# GEM_AFE_128.net
KiCad netlist of a schematic drawn in Altium Designer
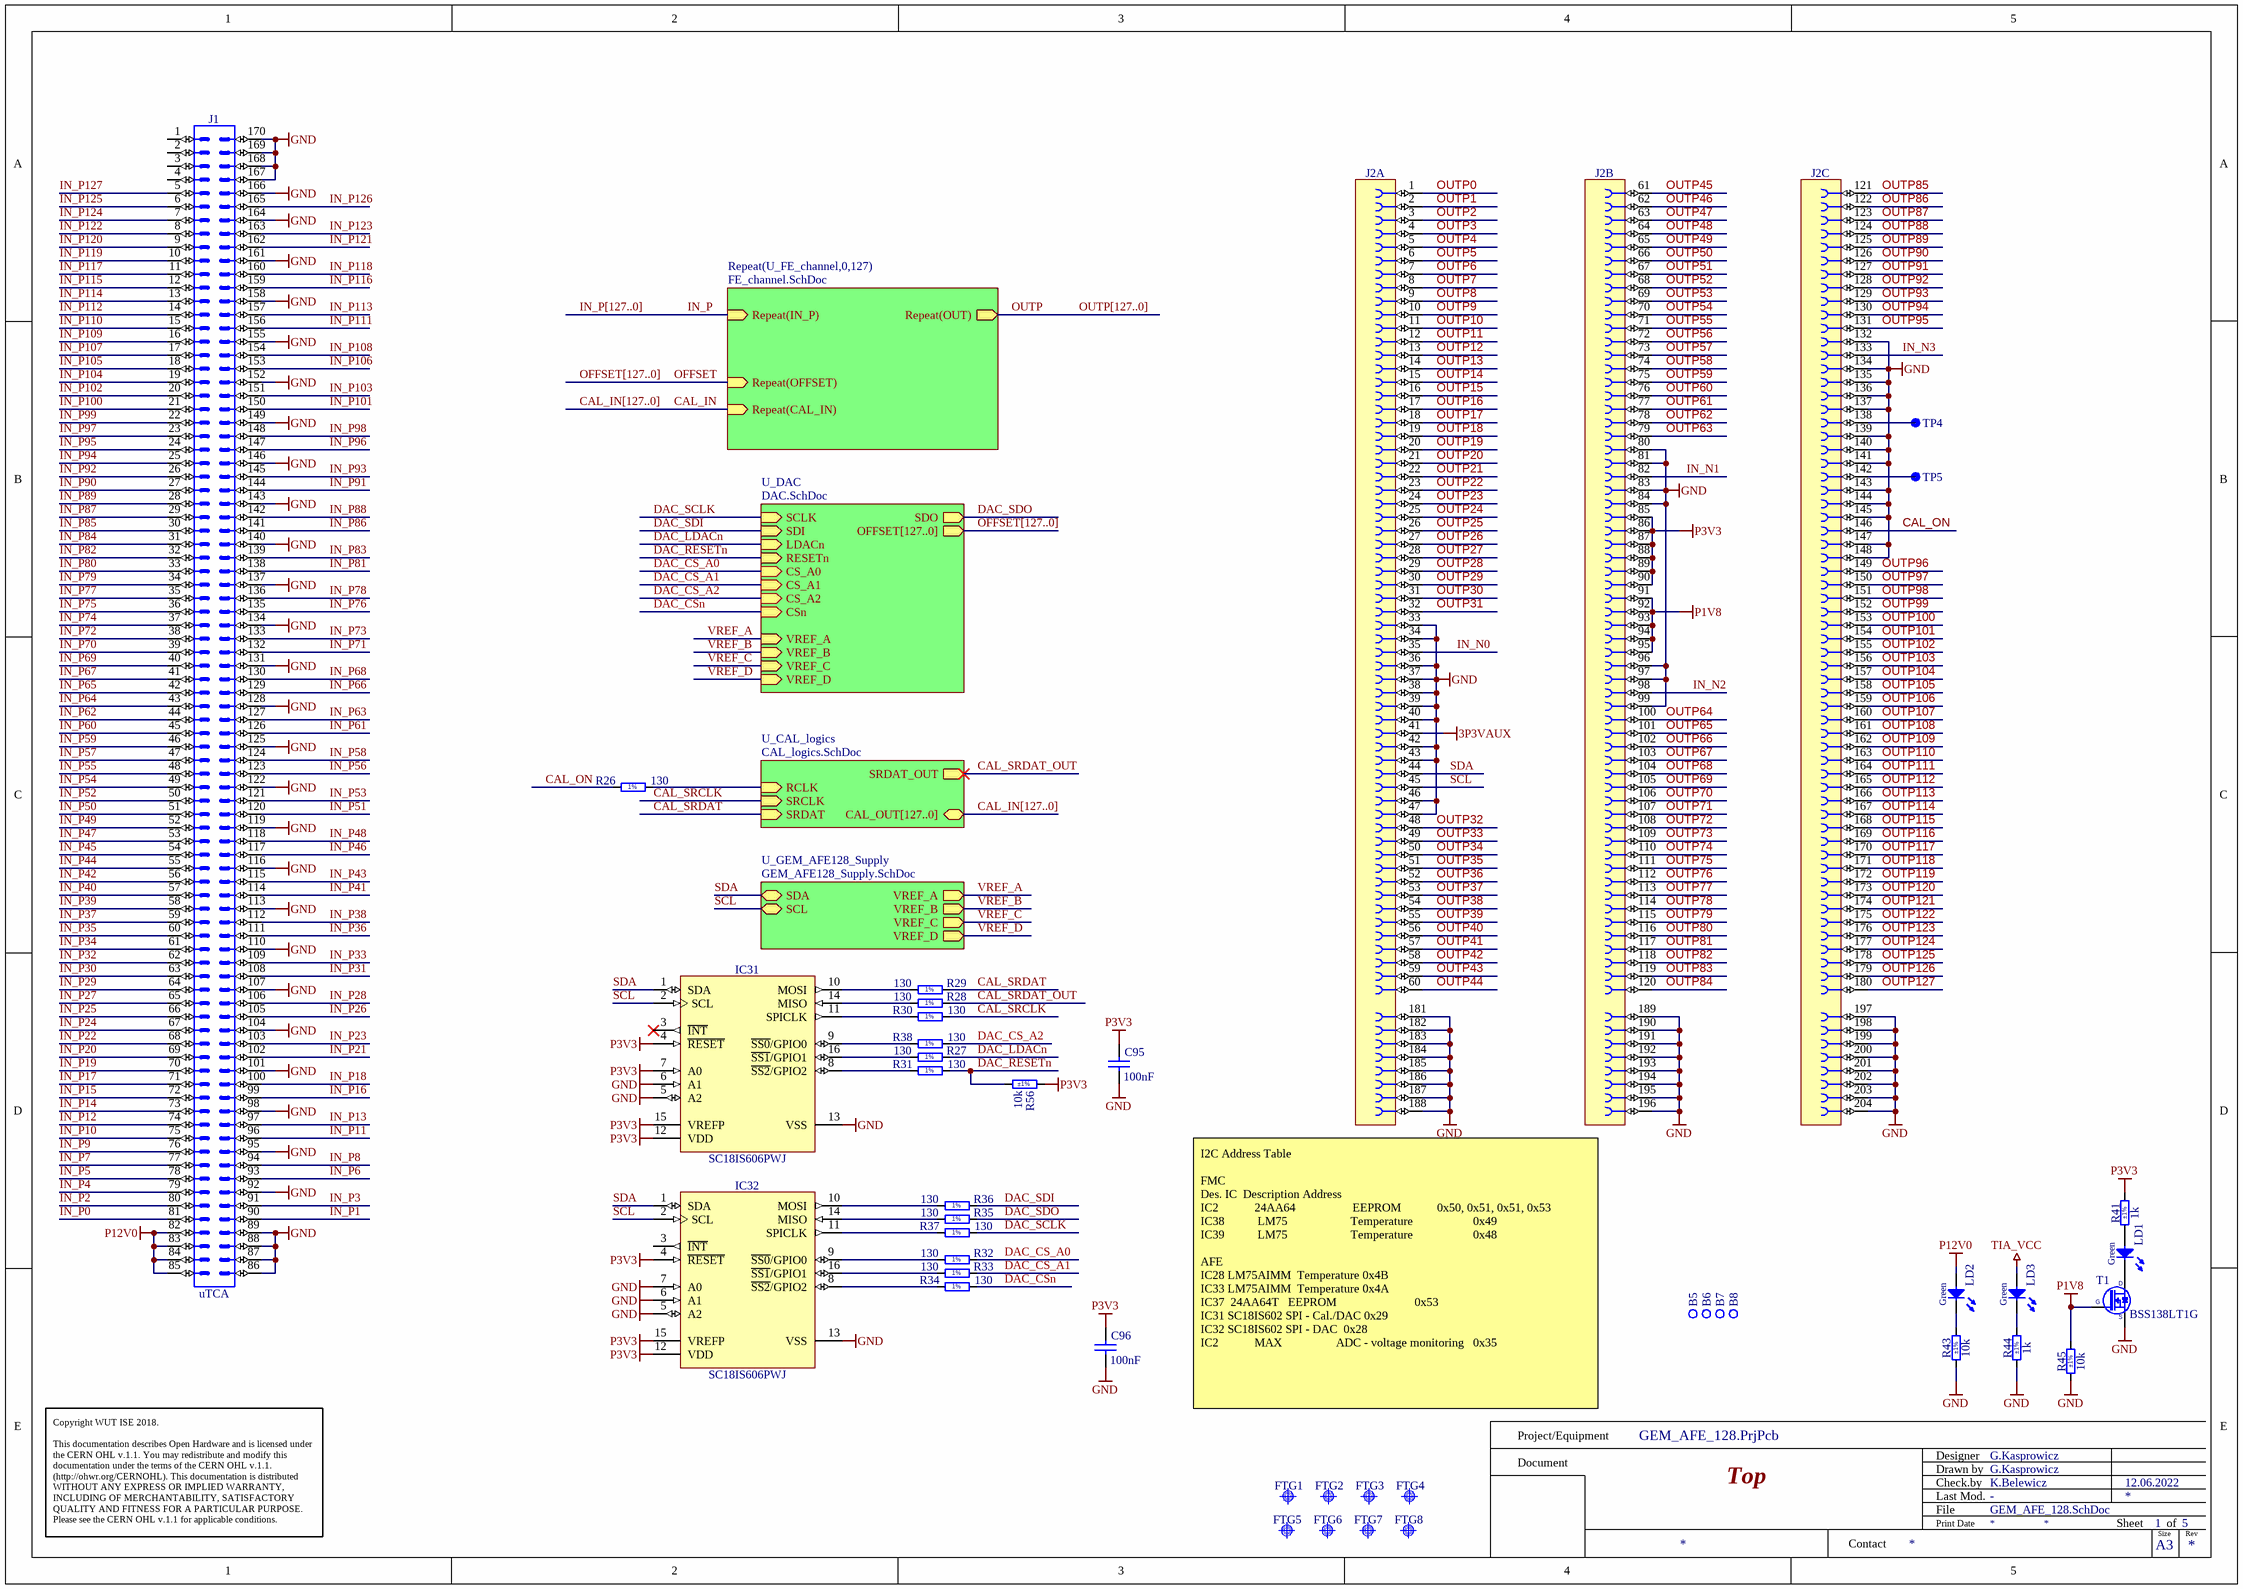
[diagram p0: GEM_AFE_128.SchDoc]

(export (version "E")
  (design (tool "Eeschema 10.0.6"))
  (components
    (comp (ref "B5")
      (value "Plated Hole")
      (footprint "MTG320_550")
      (description "Single Terminal Socket")
      (fields (field (name "PART NUMBER") "PLATED_HOLE3.2_PAD5.5") (field (name "AUTHOR") "CERN DEM JMW"))
      (libsource (lib "Eletro-mechanical") (part "Single Terminal Socket"))
    )
    (comp (ref "B6")
      (value "Plated Hole")
      (footprint "MTG320_550")
      (description "Single Terminal Socket")
      (fields (field (name "PART NUMBER") "PLATED_HOLE3.2_PAD5.5") (field (name "AUTHOR") "CERN DEM JMW"))
      (libsource (lib "Eletro-mechanical") (part "Single Terminal Socket"))
    )
    (comp (ref "B7")
      (value "Plated Hole")
      (footprint "MTG320_550")
      (description "Single Terminal Socket")
      (fields (field (name "PART NUMBER") "PLATED_HOLE3.2_PAD5.5") (field (name "AUTHOR") "CERN DEM JMW"))
      (libsource (lib "Eletro-mechanical") (part "Single Terminal Socket"))
    )
    (comp (ref "B8")
      (value "Plated Hole")
      (footprint "MTG320_550")
      (description "Single Terminal Socket")
      (fields (field (name "PART NUMBER") "PLATED_HOLE3.2_PAD5.5") (field (name "AUTHOR") "CERN DEM JMW"))
      (libsource (lib "Eletro-mechanical") (part "Single Terminal Socket"))
    )
    (comp (ref "C95")
      (value "100nF")
      (footprint "CAPC1005X55N")
      (description "Non-polarised capacitor")
      (fields
        (field (name "PART NUMBER") "CC0402_100NF_16V_10%_X7R")
        (field (name "VOLTAGE") "16V")
        (field (name "AUTHOR") "CERN DEM JLC")
      )
      (libsource (lib "Capacitors") (part "Capacitor - non polarized"))
    )
    (comp (ref "C96")
      (value "100nF")
      (footprint "CAPC1005X55N")
      (description "Non-polarised capacitor")
      (fields
        (field (name "PART NUMBER") "CC0402_100NF_16V_10%_X7R")
        (field (name "VOLTAGE") "16V")
        (field (name "AUTHOR") "CERN DEM JLC")
      )
      (libsource (lib "Capacitors") (part "Capacitor - non polarized"))
    )
    (comp (ref "FTG1")
      (value "Use only in PCB")
      (footprint "FIDUCIAL_TOP_C100-200")
      (description "Fiducial Target")
      (fields (field (name "PART NUMBER") "FIDUCIAL_TARGET_C100-200") (field (name "AUTHOR") "CERN DEM JLC"))
      (libsource (lib "Eletro-mechanical") (part "Fiducial Target"))
    )
    (comp (ref "FTG2")
      (value "Use only in PCB")
      (footprint "FIDUCIAL_TOP_C100-200")
      (description "Fiducial Target")
      (fields (field (name "PART NUMBER") "FIDUCIAL_TARGET_C100-200") (field (name "AUTHOR") "CERN DEM JLC"))
      (libsource (lib "Eletro-mechanical") (part "Fiducial Target"))
    )
    (comp (ref "FTG3")
      (value "Use only in PCB")
      (footprint "FIDUCIAL_TOP_C100-200")
      (description "Fiducial Target")
      (fields (field (name "PART NUMBER") "FIDUCIAL_TARGET_C100-200") (field (name "AUTHOR") "CERN DEM JLC"))
      (libsource (lib "Eletro-mechanical") (part "Fiducial Target"))
    )
    (comp (ref "FTG4")
      (value "Use only in PCB")
      (footprint "FIDUCIAL_TOP_C100-200")
      (description "Fiducial Target")
      (fields (field (name "PART NUMBER") "FIDUCIAL_TARGET_C100-200") (field (name "AUTHOR") "CERN DEM JLC"))
      (libsource (lib "Eletro-mechanical") (part "Fiducial Target"))
    )
    (comp (ref "FTG5")
      (value "Use only in PCB")
      (footprint "FIDUCIAL_TOP_S100-200")
      (description "Fiducial Target")
      (fields (field (name "PART NUMBER") "FIDUCIAL_TARGET_S100-200") (field (name "AUTHOR") "CERN DEM JLC"))
      (libsource (lib "Eletro-mechanical") (part "Fiducial Target"))
    )
    (comp (ref "FTG6")
      (value "Use only in PCB")
      (footprint "FIDUCIAL_TOP_S100-200")
      (description "Fiducial Target")
      (fields (field (name "PART NUMBER") "FIDUCIAL_TARGET_S100-200") (field (name "AUTHOR") "CERN DEM JLC"))
      (libsource (lib "Eletro-mechanical") (part "Fiducial Target"))
    )
    (comp (ref "FTG7")
      (value "Use only in PCB")
      (footprint "FIDUCIAL_TOP_S100-200")
      (description "Fiducial Target")
      (fields (field (name "PART NUMBER") "FIDUCIAL_TARGET_S100-200") (field (name "AUTHOR") "CERN DEM JLC"))
      (libsource (lib "Eletro-mechanical") (part "Fiducial Target"))
    )
    (comp (ref "FTG8")
      (value "Use only in PCB")
      (footprint "FIDUCIAL_TOP_S100-200")
      (description "Fiducial Target")
      (fields (field (name "PART NUMBER") "FIDUCIAL_TARGET_S100-200") (field (name "AUTHOR") "CERN DEM JLC"))
      (libsource (lib "Eletro-mechanical") (part "Fiducial Target"))
    )
    (comp (ref "IC31")
      (value "SC18IS606PWJ")
      (footprint "SOP65P640X110-16N")
      (description "I2C-bus to SPI bridge")
      (fields (field (name "MANUFACTURER") "NXP SEMICONDUCTORS") (field (name "AUTHOR") "GK"))
      (libsource (lib "ICS-logic") (part "SC18IS606PWJ"))
    )
    (comp (ref "IC32")
      (value "SC18IS606PWJ")
      (footprint "SOP65P640X110-16N")
      (description "I2C-bus to SPI bridge")
      (fields (field (name "MANUFACTURER") "NXP SEMICONDUCTORS") (field (name "AUTHOR") "GK"))
      (libsource (lib "ICS-logic") (part "SC18IS606PWJ"))
    )
    (comp (ref "J1")
      (value "uTCA")
      (footprint "MICRO-TCA")
      (description "170 Contact MicroTCA (Telecom Computing Architecture) Board Edge Connector")
      (fields
        (field (name "PART NUMBER") "PICMG_uTCA.0_R1.0.")
        (field (name "MANUFACTURER") "PICMG")
        (field (name "AUTHOR") "CERN DEM JLC")
      )
      (libsource (lib "Connectors") (part "Micro TCA Male 170"))
    )
    (comp (ref "J2")
      (value "~")
      (footprint "SAMTEC_QSH-090-01-F-D-RA")
      (description "Connector 180 Female (3x60) + 3x8 GND")
      (fields
        (field (name "PART NUMBER") "SAMTEC_QSH-090-01-F-D-RA")
        (field (name "MANUFACTURER") "SAMTEC")
        (field (name "AUTHOR") "CERN DEM HF")
      )
      (libsource (lib "Connectors") (part "Connector 180 Female (3x60) + 3x8 GND"))
    )
    (comp (ref "LD1")
      (value "Green")
      (footprint "LED_KINGBRIGHT_KPA-1606CGCK")
      (description "LED Green 1C 2A")
      (fields
        (field (name "PART NUMBER") "LED_KINGBRIGHT_KPA-1606CGCK")
        (field (name "MANUFACTURER") "KINGBRIGHT")
        (field (name "AUTHOR") "CERN DEM MR")
      )
      (libsource (lib "ICs And Semiconductors") (part "LED Green 1C 2A"))
    )
    (comp (ref "LD2")
      (value "Green")
      (footprint "LED_KINGBRIGHT_KPA-1606CGCK")
      (description "LED Green 1C 2A")
      (fields
        (field (name "PART NUMBER") "LED_KINGBRIGHT_KPA-1606CGCK")
        (field (name "MANUFACTURER") "KINGBRIGHT")
        (field (name "AUTHOR") "CERN DEM MR")
      )
      (libsource (lib "ICs And Semiconductors") (part "LED Green 1C 2A"))
    )
    (comp (ref "LD3")
      (value "Green")
      (footprint "LED_KINGBRIGHT_KPA-1606CGCK")
      (description "LED Green 1C 2A")
      (fields
        (field (name "PART NUMBER") "LED_KINGBRIGHT_KPA-1606CGCK")
        (field (name "MANUFACTURER") "KINGBRIGHT")
        (field (name "AUTHOR") "CERN DEM MR")
      )
      (libsource (lib "ICs And Semiconductors") (part "LED Green 1C 2A"))
    )
    (comp (ref "R26")
      (value "130")
      (footprint "RESC1005X40N")
      (description "Resistor - 1%")
      (fields
        (field (name "PART NUMBER") "R0402_130R_1%_0.0625W_100PPM")
        (field (name "POWER") "0.0625W")
        (field (name "AUTHOR") "CERN DEM JLC")
      )
      (libsource (lib "Resistors") (part "Resistor - 1%"))
    )
    (comp (ref "R27")
      (value "130")
      (footprint "RESC1005X40N")
      (description "Resistor - 1%")
      (fields
        (field (name "PART NUMBER") "R0402_130R_1%_0.0625W_100PPM")
        (field (name "POWER") "0.0625W")
        (field (name "AUTHOR") "CERN DEM JLC")
      )
      (libsource (lib "Resistors") (part "Resistor - 1%"))
    )
    (comp (ref "R28")
      (value "130")
      (footprint "RESC1005X40N")
      (description "Resistor - 1%")
      (fields
        (field (name "PART NUMBER") "R0402_130R_1%_0.0625W_100PPM")
        (field (name "POWER") "0.0625W")
        (field (name "AUTHOR") "CERN DEM JLC")
      )
      (libsource (lib "Resistors") (part "Resistor - 1%"))
    )
    (comp (ref "R29")
      (value "130")
      (footprint "RESC1005X40N")
      (description "Resistor - 1%")
      (fields
        (field (name "PART NUMBER") "R0402_130R_1%_0.0625W_100PPM")
        (field (name "POWER") "0.0625W")
        (field (name "AUTHOR") "CERN DEM JLC")
      )
      (libsource (lib "Resistors") (part "Resistor - 1%"))
    )
    (comp (ref "R30")
      (value "130")
      (footprint "RESC1005X40N")
      (description "Resistor - 1%")
      (fields
        (field (name "PART NUMBER") "R0402_130R_1%_0.0625W_100PPM")
        (field (name "POWER") "0.0625W")
        (field (name "AUTHOR") "CERN DEM JLC")
      )
      (libsource (lib "Resistors") (part "Resistor - 1%"))
    )
    (comp (ref "R31")
      (value "130")
      (footprint "RESC1005X40N")
      (description "Resistor - 1%")
      (fields
        (field (name "PART NUMBER") "R0402_130R_1%_0.0625W_100PPM")
        (field (name "POWER") "0.0625W")
        (field (name "AUTHOR") "CERN DEM JLC")
      )
      (libsource (lib "Resistors") (part "Resistor - 1%"))
    )
    (comp (ref "R32")
      (value "130")
      (footprint "RESC1005X40N")
      (description "Resistor - 1%")
      (fields
        (field (name "PART NUMBER") "R0402_130R_1%_0.0625W_100PPM")
        (field (name "POWER") "0.0625W")
        (field (name "AUTHOR") "CERN DEM JLC")
      )
      (libsource (lib "Resistors") (part "Resistor - 1%"))
    )
    (comp (ref "R33")
      (value "130")
      (footprint "RESC1005X40N")
      (description "Resistor - 1%")
      (fields
        (field (name "PART NUMBER") "R0402_130R_1%_0.0625W_100PPM")
        (field (name "POWER") "0.0625W")
        (field (name "AUTHOR") "CERN DEM JLC")
      )
      (libsource (lib "Resistors") (part "Resistor - 1%"))
    )
    (comp (ref "R34")
      (value "130")
      (footprint "RESC1005X40N")
      (description "Resistor - 1%")
      (fields
        (field (name "PART NUMBER") "R0402_130R_1%_0.0625W_100PPM")
        (field (name "POWER") "0.0625W")
        (field (name "AUTHOR") "CERN DEM JLC")
      )
      (libsource (lib "Resistors") (part "Resistor - 1%"))
    )
    (comp (ref "R35")
      (value "130")
      (footprint "RESC1005X40N")
      (description "Resistor - 1%")
      (fields
        (field (name "PART NUMBER") "R0402_130R_1%_0.0625W_100PPM")
        (field (name "POWER") "0.0625W")
        (field (name "AUTHOR") "CERN DEM JLC")
      )
      (libsource (lib "Resistors") (part "Resistor - 1%"))
    )
    (comp (ref "R36")
      (value "130")
      (footprint "RESC1005X40N")
      (description "Resistor - 1%")
      (fields
        (field (name "PART NUMBER") "R0402_130R_1%_0.0625W_100PPM")
        (field (name "POWER") "0.0625W")
        (field (name "AUTHOR") "CERN DEM JLC")
      )
      (libsource (lib "Resistors") (part "Resistor - 1%"))
    )
    (comp (ref "R37")
      (value "130")
      (footprint "RESC1005X40N")
      (description "Resistor - 1%")
      (fields
        (field (name "PART NUMBER") "R0402_130R_1%_0.0625W_100PPM")
        (field (name "POWER") "0.0625W")
        (field (name "AUTHOR") "CERN DEM JLC")
      )
      (libsource (lib "Resistors") (part "Resistor - 1%"))
    )
    (comp (ref "R38")
      (value "130")
      (footprint "RESC1005X40N")
      (description "Resistor - 1%")
      (fields
        (field (name "PART NUMBER") "R0402_130R_1%_0.0625W_100PPM")
        (field (name "POWER") "0.0625W")
        (field (name "AUTHOR") "CERN DEM JLC")
      )
      (libsource (lib "Resistors") (part "Resistor - 1%"))
    )
    (comp (ref "R41")
      (value "1k")
      (footprint "RESC1005X40N")
      (description "Resistor - 1%")
      (fields
        (field (name "TOLERANCE") "±1%")
        (field (name "PART NUMBER") "R0402_1K_1%_0.0625W_100PPM")
        (field (name "POWER") "0.0625W")
        (field (name "AUTHOR") "CERN DEM JLC")
      )
      (libsource (lib "Resistors") (part "Resistor - 1%"))
    )
    (comp (ref "R43")
      (value "10k")
      (footprint "RESC1005X40N")
      (description "Resistor - 1%")
      (fields
        (field (name "TOLERANCE") "±1%")
        (field (name "PART NUMBER") "R0402_10K_1%_0.0625W_100PPM")
        (field (name "POWER") "0.0625W")
        (field (name "AUTHOR") "CERN DEM JLC")
      )
      (libsource (lib "Resistors") (part "Resistor - 1%"))
    )
    (comp (ref "R44")
      (value "1k")
      (footprint "RESC1005X40N")
      (description "Resistor - 1%")
      (fields
        (field (name "TOLERANCE") "±1%")
        (field (name "PART NUMBER") "R0402_1K_1%_0.0625W_100PPM")
        (field (name "POWER") "0.0625W")
        (field (name "AUTHOR") "CERN DEM JLC")
      )
      (libsource (lib "Resistors") (part "Resistor - 1%"))
    )
    (comp (ref "R45")
      (value "10k")
      (footprint "RESC1005X40N")
      (description "Resistor - 1%")
      (fields
        (field (name "TOLERANCE") "±1%")
        (field (name "PART NUMBER") "R0402_10K_1%_0.0625W_100PPM")
        (field (name "POWER") "0.0625W")
        (field (name "AUTHOR") "CERN DEM JLC")
      )
      (libsource (lib "Resistors") (part "Resistor - 1%"))
    )
    (comp (ref "R56")
      (value "10k")
      (footprint "RESC1005X40N")
      (description "Resistor - 1%")
      (fields
        (field (name "TOLERANCE") "±1%")
        (field (name "PART NUMBER") "R0402_10K_1%_0.0625W_100PPM")
        (field (name "POWER") "0.0625W")
        (field (name "AUTHOR") "CERN DEM JLC")
      )
      (libsource (lib "Resistors") (part "Resistor - 1%"))
    )
    (comp (ref "T1")
      (value "BSS138LT1G")
      (footprint "SOT95P240X110-3N")
      (description "N-CHANNEL MOSFET WITH DIODE")
      (fields
        (field (name "MANUFACTURER") "ON SEMICONDUCTOR")
        (field (name "MANUFACTURER PART NUMBER") "BSS138L")
        (field (name "AUTHOR") "CERN DEM JLC")
      )
      (libsource (lib "ICs And Semiconductors") (part "N-MOSFET-D 1G 2S 3D"))
    )
    (comp (ref "TP4")
      (value "SMD Pad")
      (footprint "C100")
      (description "Pad")
      (fields (field (name "PART NUMBER") "SMD_PAD_D1MM") (field (name "AUTHOR") "CERN DEM JLC"))
      (libsource (lib "Eletro-mechanical") (part "Single SMD Pad (Round)"))
    )
    (comp (ref "TP5")
      (value "SMD Pad")
      (footprint "C100")
      (description "Pad")
      (fields (field (name "PART NUMBER") "SMD_PAD_D1MM") (field (name "AUTHOR") "CERN DEM JLC"))
      (libsource (lib "Eletro-mechanical") (part "Single SMD Pad (Round)"))
    )
  )
  (nets
    (net (code "259") (name "/CAL_ON") (class "Default")
      (node (ref "J2") (pin "146") (pinfunction "146_146") (pintype "bidirectional"))
      (node (ref "R26") (pin "1") (pinfunction "1_1") (pintype "passive"))
    )
    (net (code "260") (name "/CAL_SRCLK") (class "Default")
      (node (ref "R30") (pin "2") (pinfunction "2_2") (pintype "passive"))
    )
    (net (code "261") (name "/CAL_SRDAT") (class "Default")
      (node (ref "R29") (pin "1") (pinfunction "1_1") (pintype "passive"))
    )
    (net (code "262") (name "/CAL_SRDAT_OUT") (class "Default")
      (node (ref "R28") (pin "1") (pinfunction "1_1") (pintype "passive"))
    )
    (net (code "263") (name "/DAC_CS_A0") (class "Default")
      (node (ref "R32") (pin "1") (pinfunction "1_1") (pintype "passive"))
    )
    (net (code "264") (name "/DAC_CS_A1") (class "Default")
      (node (ref "R33") (pin "1") (pinfunction "1_1") (pintype "passive"))
    )
    (net (code "265") (name "/DAC_CS_A2") (class "Default")
      (node (ref "R38") (pin "2") (pinfunction "2_2") (pintype "passive"))
    )
    (net (code "266") (name "/DAC_CSn") (class "Default")
      (node (ref "R34") (pin "2") (pinfunction "2_2") (pintype "passive"))
    )
    (net (code "267") (name "/DAC_LDACn") (class "Default")
      (node (ref "R27") (pin "1") (pinfunction "1_1") (pintype "passive"))
    )
    (net (code "268") (name "/DAC_RESETn") (class "Default")
      (node (ref "R31") (pin "2") (pinfunction "2_2") (pintype "passive"))
      (node (ref "R56") (pin "1") (pinfunction "1_1") (pintype "passive"))
    )
    (net (code "269") (name "/DAC_SCLK") (class "Default")
      (node (ref "R37") (pin "2") (pinfunction "2_2") (pintype "passive"))
    )
    (net (code "270") (name "/DAC_SDI") (class "Default")
      (node (ref "R36") (pin "1") (pinfunction "1_1") (pintype "passive"))
    )
    (net (code "271") (name "/DAC_SDO") (class "Default")
      (node (ref "R35") (pin "1") (pinfunction "1_1") (pintype "passive"))
    )
    (net (code "272") (name "/IN_N0") (class "Default")
      (node (ref "J2") (pin "35") (pinfunction "35_35") (pintype "bidirectional"))
    )
    (net (code "273") (name "/IN_N1") (class "Default")
      (node (ref "J2") (pin "82") (pinfunction "82_82") (pintype "bidirectional"))
    )
    (net (code "274") (name "/IN_N2") (class "Default")
      (node (ref "J2") (pin "98") (pinfunction "98_98") (pintype "bidirectional"))
    )
    (net (code "275") (name "/IN_N3") (class "Default")
      (node (ref "J2") (pin "133") (pinfunction "133_133") (pintype "bidirectional"))
    )
    (net (code "277") (name "/IN_P0") (class "Default")
      (node (ref "J1") (pin "81") (pinfunction "81_81") (pintype "bidirectional"))
    )
    (net (code "278") (name "/IN_P1") (class "Default")
      (node (ref "J1") (pin "90") (pinfunction "90_90") (pintype "bidirectional"))
    )
    (net (code "279") (name "/IN_P2") (class "Default")
      (node (ref "J1") (pin "80") (pinfunction "80_80") (pintype "bidirectional"))
    )
    (net (code "280") (name "/IN_P3") (class "Default")
      (node (ref "J1") (pin "91") (pinfunction "91_91") (pintype "bidirectional"))
    )
    (net (code "281") (name "/IN_P4") (class "Default")
      (node (ref "J1") (pin "79") (pinfunction "79_79") (pintype "bidirectional"))
    )
    (net (code "282") (name "/IN_P5") (class "Default")
      (node (ref "J1") (pin "78") (pinfunction "78_78") (pintype "bidirectional"))
    )
    (net (code "283") (name "/IN_P6") (class "Default")
      (node (ref "J1") (pin "93") (pinfunction "93_93") (pintype "bidirectional"))
    )
    (net (code "284") (name "/IN_P7") (class "Default")
      (node (ref "J1") (pin "77") (pinfunction "77_77") (pintype "bidirectional"))
    )
    (net (code "285") (name "/IN_P8") (class "Default")
      (node (ref "J1") (pin "94") (pinfunction "94_94") (pintype "bidirectional"))
    )
    (net (code "286") (name "/IN_P9") (class "Default")
      (node (ref "J1") (pin "76") (pinfunction "76_76") (pintype "bidirectional"))
    )
    (net (code "287") (name "/IN_P10") (class "Default")
      (node (ref "J1") (pin "75") (pinfunction "75_75") (pintype "bidirectional"))
    )
    (net (code "288") (name "/IN_P11") (class "Default")
      (node (ref "J1") (pin "96") (pinfunction "96_96") (pintype "bidirectional"))
    )
    (net (code "289") (name "/IN_P12") (class "Default")
      (node (ref "J1") (pin "74") (pinfunction "74_74") (pintype "bidirectional"))
    )
    (net (code "290") (name "/IN_P13") (class "Default")
      (node (ref "J1") (pin "97") (pinfunction "97_97") (pintype "bidirectional"))
    )
    (net (code "291") (name "/IN_P14") (class "Default")
      (node (ref "J1") (pin "73") (pinfunction "73_73") (pintype "bidirectional"))
    )
    (net (code "292") (name "/IN_P15") (class "Default")
      (node (ref "J1") (pin "72") (pinfunction "72_72") (pintype "bidirectional"))
    )
    (net (code "293") (name "/IN_P16") (class "Default")
      (node (ref "J1") (pin "99") (pinfunction "99_99") (pintype "bidirectional"))
    )
    (net (code "294") (name "/IN_P17") (class "Default")
      (node (ref "J1") (pin "71") (pinfunction "71_71") (pintype "bidirectional"))
    )
    (net (code "295") (name "/IN_P18") (class "Default")
      (node (ref "J1") (pin "100") (pinfunction "100_100") (pintype "bidirectional"))
    )
    (net (code "296") (name "/IN_P19") (class "Default")
      (node (ref "J1") (pin "70") (pinfunction "70_70") (pintype "bidirectional"))
    )
    (net (code "297") (name "/IN_P20") (class "Default")
      (node (ref "J1") (pin "69") (pinfunction "69_69") (pintype "bidirectional"))
    )
    (net (code "298") (name "/IN_P21") (class "Default")
      (node (ref "J1") (pin "102") (pinfunction "102_102") (pintype "bidirectional"))
    )
    (net (code "299") (name "/IN_P22") (class "Default")
      (node (ref "J1") (pin "68") (pinfunction "68_68") (pintype "bidirectional"))
    )
    (net (code "300") (name "/IN_P23") (class "Default")
      (node (ref "J1") (pin "103") (pinfunction "103_103") (pintype "bidirectional"))
    )
    (net (code "301") (name "/IN_P24") (class "Default")
      (node (ref "J1") (pin "67") (pinfunction "67_67") (pintype "bidirectional"))
    )
    (net (code "302") (name "/IN_P25") (class "Default")
      (node (ref "J1") (pin "66") (pinfunction "66_66") (pintype "bidirectional"))
    )
    (net (code "303") (name "/IN_P26") (class "Default")
      (node (ref "J1") (pin "105") (pinfunction "105_105") (pintype "bidirectional"))
    )
    (net (code "304") (name "/IN_P27") (class "Default")
      (node (ref "J1") (pin "65") (pinfunction "65_65") (pintype "bidirectional"))
    )
    (net (code "305") (name "/IN_P28") (class "Default")
      (node (ref "J1") (pin "106") (pinfunction "106_106") (pintype "bidirectional"))
    )
    (net (code "306") (name "/IN_P29") (class "Default")
      (node (ref "J1") (pin "64") (pinfunction "64_64") (pintype "bidirectional"))
    )
    (net (code "307") (name "/IN_P30") (class "Default")
      (node (ref "J1") (pin "63") (pinfunction "63_63") (pintype "bidirectional"))
    )
    (net (code "308") (name "/IN_P31") (class "Default")
      (node (ref "J1") (pin "108") (pinfunction "108_108") (pintype "bidirectional"))
    )
    (net (code "309") (name "/IN_P32") (class "Default")
      (node (ref "J1") (pin "62") (pinfunction "62_62") (pintype "bidirectional"))
    )
    (net (code "310") (name "/IN_P33") (class "Default")
      (node (ref "J1") (pin "109") (pinfunction "109_109") (pintype "bidirectional"))
    )
    (net (code "311") (name "/IN_P34") (class "Default")
      (node (ref "J1") (pin "61") (pinfunction "61_61") (pintype "bidirectional"))
    )
    (net (code "312") (name "/IN_P35") (class "Default")
      (node (ref "J1") (pin "60") (pinfunction "60_60") (pintype "bidirectional"))
    )
    (net (code "313") (name "/IN_P36") (class "Default")
      (node (ref "J1") (pin "111") (pinfunction "111_111") (pintype "bidirectional"))
    )
    (net (code "314") (name "/IN_P37") (class "Default")
      (node (ref "J1") (pin "59") (pinfunction "59_59") (pintype "bidirectional"))
    )
    (net (code "315") (name "/IN_P38") (class "Default")
      (node (ref "J1") (pin "112") (pinfunction "112_112") (pintype "bidirectional"))
    )
    (net (code "316") (name "/IN_P39") (class "Default")
      (node (ref "J1") (pin "58") (pinfunction "58_58") (pintype "bidirectional"))
    )
    (net (code "317") (name "/IN_P40") (class "Default")
      (node (ref "J1") (pin "57") (pinfunction "57_57") (pintype "bidirectional"))
    )
    (net (code "318") (name "/IN_P41") (class "Default")
      (node (ref "J1") (pin "114") (pinfunction "114_114") (pintype "bidirectional"))
    )
    (net (code "319") (name "/IN_P42") (class "Default")
      (node (ref "J1") (pin "56") (pinfunction "56_56") (pintype "bidirectional"))
    )
    (net (code "320") (name "/IN_P43") (class "Default")
      (node (ref "J1") (pin "115") (pinfunction "115_115") (pintype "bidirectional"))
    )
    (net (code "321") (name "/IN_P44") (class "Default")
      (node (ref "J1") (pin "55") (pinfunction "55_55") (pintype "bidirectional"))
    )
    (net (code "322") (name "/IN_P45") (class "Default")
      (node (ref "J1") (pin "54") (pinfunction "54_54") (pintype "bidirectional"))
    )
    (net (code "323") (name "/IN_P46") (class "Default")
      (node (ref "J1") (pin "117") (pinfunction "117_117") (pintype "bidirectional"))
    )
    (net (code "324") (name "/IN_P47") (class "Default")
      (node (ref "J1") (pin "53") (pinfunction "53_53") (pintype "bidirectional"))
    )
    (net (code "325") (name "/IN_P48") (class "Default")
      (node (ref "J1") (pin "118") (pinfunction "118_118") (pintype "bidirectional"))
    )
    (net (code "326") (name "/IN_P49") (class "Default")
      (node (ref "J1") (pin "52") (pinfunction "52_52") (pintype "bidirectional"))
    )
    (net (code "327") (name "/IN_P50") (class "Default")
      (node (ref "J1") (pin "51") (pinfunction "51_51") (pintype "bidirectional"))
    )
    (net (code "328") (name "/IN_P51") (class "Default")
      (node (ref "J1") (pin "120") (pinfunction "120_120") (pintype "bidirectional"))
    )
    (net (code "329") (name "/IN_P52") (class "Default")
      (node (ref "J1") (pin "50") (pinfunction "50_50") (pintype "bidirectional"))
    )
    (net (code "330") (name "/IN_P53") (class "Default")
      (node (ref "J1") (pin "121") (pinfunction "121_121") (pintype "bidirectional"))
    )
    (net (code "331") (name "/IN_P54") (class "Default")
      (node (ref "J1") (pin "49") (pinfunction "49_49") (pintype "bidirectional"))
    )
    (net (code "332") (name "/IN_P55") (class "Default")
      (node (ref "J1") (pin "48") (pinfunction "48_48") (pintype "bidirectional"))
    )
    (net (code "333") (name "/IN_P56") (class "Default")
      (node (ref "J1") (pin "123") (pinfunction "123_123") (pintype "bidirectional"))
    )
    (net (code "334") (name "/IN_P57") (class "Default")
      (node (ref "J1") (pin "47") (pinfunction "47_47") (pintype "bidirectional"))
    )
    (net (code "335") (name "/IN_P58") (class "Default")
      (node (ref "J1") (pin "124") (pinfunction "124_124") (pintype "bidirectional"))
    )
    (net (code "336") (name "/IN_P59") (class "Default")
      (node (ref "J1") (pin "46") (pinfunction "46_46") (pintype "bidirectional"))
    )
    (net (code "337") (name "/IN_P60") (class "Default")
      (node (ref "J1") (pin "45") (pinfunction "45_45") (pintype "bidirectional"))
    )
    (net (code "338") (name "/IN_P61") (class "Default")
      (node (ref "J1") (pin "126") (pinfunction "126_126") (pintype "bidirectional"))
    )
    (net (code "339") (name "/IN_P62") (class "Default")
      (node (ref "J1") (pin "44") (pinfunction "44_44") (pintype "bidirectional"))
    )
    (net (code "340") (name "/IN_P63") (class "Default")
      (node (ref "J1") (pin "127") (pinfunction "127_127") (pintype "bidirectional"))
    )
    (net (code "341") (name "/IN_P64") (class "Default")
      (node (ref "J1") (pin "43") (pinfunction "43_43") (pintype "bidirectional"))
    )
    (net (code "342") (name "/IN_P65") (class "Default")
      (node (ref "J1") (pin "42") (pinfunction "42_42") (pintype "bidirectional"))
    )
    (net (code "343") (name "/IN_P66") (class "Default")
      (node (ref "J1") (pin "129") (pinfunction "129_129") (pintype "bidirectional"))
    )
    (net (code "344") (name "/IN_P67") (class "Default")
      (node (ref "J1") (pin "41") (pinfunction "41_41") (pintype "bidirectional"))
    )
    (net (code "345") (name "/IN_P68") (class "Default")
      (node (ref "J1") (pin "130") (pinfunction "130_130") (pintype "bidirectional"))
    )
    (net (code "346") (name "/IN_P69") (class "Default")
      (node (ref "J1") (pin "40") (pinfunction "40_40") (pintype "bidirectional"))
    )
    (net (code "347") (name "/IN_P70") (class "Default")
      (node (ref "J1") (pin "39") (pinfunction "39_39") (pintype "bidirectional"))
    )
    (net (code "348") (name "/IN_P71") (class "Default")
      (node (ref "J1") (pin "132") (pinfunction "132_132") (pintype "bidirectional"))
    )
    (net (code "349") (name "/IN_P72") (class "Default")
      (node (ref "J1") (pin "38") (pinfunction "38_38") (pintype "bidirectional"))
    )
    (net (code "350") (name "/IN_P73") (class "Default")
      (node (ref "J1") (pin "133") (pinfunction "133_133") (pintype "bidirectional"))
    )
    (net (code "351") (name "/IN_P74") (class "Default")
      (node (ref "J1") (pin "37") (pinfunction "37_37") (pintype "bidirectional"))
    )
    (net (code "352") (name "/IN_P75") (class "Default")
      (node (ref "J1") (pin "36") (pinfunction "36_36") (pintype "bidirectional"))
    )
    (net (code "353") (name "/IN_P76") (class "Default")
      (node (ref "J1") (pin "135") (pinfunction "135_135") (pintype "bidirectional"))
    )
    (net (code "354") (name "/IN_P77") (class "Default")
      (node (ref "J1") (pin "35") (pinfunction "35_35") (pintype "bidirectional"))
    )
    (net (code "355") (name "/IN_P78") (class "Default")
      (node (ref "J1") (pin "136") (pinfunction "136_136") (pintype "bidirectional"))
    )
    (net (code "356") (name "/IN_P79") (class "Default")
      (node (ref "J1") (pin "34") (pinfunction "34_34") (pintype "bidirectional"))
    )
    (net (code "357") (name "/IN_P80") (class "Default")
      (node (ref "J1") (pin "33") (pinfunction "33_33") (pintype "bidirectional"))
    )
    (net (code "358") (name "/IN_P81") (class "Default")
      (node (ref "J1") (pin "138") (pinfunction "138_138") (pintype "bidirectional"))
    )
    (net (code "359") (name "/IN_P82") (class "Default")
      (node (ref "J1") (pin "32") (pinfunction "32_32") (pintype "bidirectional"))
    )
    (net (code "360") (name "/IN_P83") (class "Default")
      (node (ref "J1") (pin "139") (pinfunction "139_139") (pintype "bidirectional"))
    )
    (net (code "361") (name "/IN_P84") (class "Default")
      (node (ref "J1") (pin "31") (pinfunction "31_31") (pintype "bidirectional"))
    )
    (net (code "362") (name "/IN_P85") (class "Default")
      (node (ref "J1") (pin "30") (pinfunction "30_30") (pintype "bidirectional"))
    )
    (net (code "363") (name "/IN_P86") (class "Default")
      (node (ref "J1") (pin "141") (pinfunction "141_141") (pintype "bidirectional"))
    )
    (net (code "364") (name "/IN_P87") (class "Default")
      (node (ref "J1") (pin "29") (pinfunction "29_29") (pintype "bidirectional"))
    )
    (net (code "365") (name "/IN_P88") (class "Default")
      (node (ref "J1") (pin "142") (pinfunction "142_142") (pintype "bidirectional"))
    )
    (net (code "366") (name "/IN_P89") (class "Default")
      (node (ref "J1") (pin "28") (pinfunction "28_28") (pintype "bidirectional"))
    )
    (net (code "367") (name "/IN_P90") (class "Default")
      (node (ref "J1") (pin "27") (pinfunction "27_27") (pintype "bidirectional"))
    )
    (net (code "368") (name "/IN_P91") (class "Default")
      (node (ref "J1") (pin "144") (pinfunction "144_144") (pintype "bidirectional"))
    )
    (net (code "369") (name "/IN_P92") (class "Default")
      (node (ref "J1") (pin "26") (pinfunction "26_26") (pintype "bidirectional"))
    )
    (net (code "370") (name "/IN_P93") (class "Default")
      (node (ref "J1") (pin "145") (pinfunction "145_145") (pintype "bidirectional"))
    )
    (net (code "371") (name "/IN_P94") (class "Default")
      (node (ref "J1") (pin "25") (pinfunction "25_25") (pintype "bidirectional"))
    )
    (net (code "372") (name "/IN_P95") (class "Default")
      (node (ref "J1") (pin "24") (pinfunction "24_24") (pintype "bidirectional"))
    )
    (net (code "373") (name "/IN_P96") (class "Default")
      (node (ref "J1") (pin "147") (pinfunction "147_147") (pintype "bidirectional"))
    )
    (net (code "374") (name "/IN_P97") (class "Default")
      (node (ref "J1") (pin "23") (pinfunction "23_23") (pintype "bidirectional"))
    )
    (net (code "375") (name "/IN_P98") (class "Default")
      (node (ref "J1") (pin "148") (pinfunction "148_148") (pintype "bidirectional"))
    )
    (net (code "376") (name "/IN_P99") (class "Default")
      (node (ref "J1") (pin "22") (pinfunction "22_22") (pintype "bidirectional"))
    )
    (net (code "377") (name "/IN_P100") (class "Default")
      (node (ref "J1") (pin "21") (pinfunction "21_21") (pintype "bidirectional"))
    )
    (net (code "378") (name "/IN_P101") (class "Default")
      (node (ref "J1") (pin "150") (pinfunction "150_150") (pintype "bidirectional"))
    )
    (net (code "379") (name "/IN_P102") (class "Default")
      (node (ref "J1") (pin "20") (pinfunction "20_20") (pintype "bidirectional"))
    )
    (net (code "380") (name "/IN_P103") (class "Default")
      (node (ref "J1") (pin "151") (pinfunction "151_151") (pintype "bidirectional"))
    )
    (net (code "381") (name "/IN_P104") (class "Default")
      (node (ref "J1") (pin "19") (pinfunction "19_19") (pintype "bidirectional"))
    )
    (net (code "382") (name "/IN_P105") (class "Default")
      (node (ref "J1") (pin "18") (pinfunction "18_18") (pintype "bidirectional"))
    )
    (net (code "383") (name "/IN_P106") (class "Default")
      (node (ref "J1") (pin "153") (pinfunction "153_153") (pintype "bidirectional"))
    )
    (net (code "384") (name "/IN_P107") (class "Default")
      (node (ref "J1") (pin "17") (pinfunction "17_17") (pintype "bidirectional"))
    )
    (net (code "385") (name "/IN_P108") (class "Default")
      (node (ref "J1") (pin "154") (pinfunction "154_154") (pintype "bidirectional"))
    )
    (net (code "386") (name "/IN_P109") (class "Default")
      (node (ref "J1") (pin "16") (pinfunction "16_16") (pintype "bidirectional"))
    )
    (net (code "387") (name "/IN_P110") (class "Default")
      (node (ref "J1") (pin "15") (pinfunction "15_15") (pintype "bidirectional"))
    )
    (net (code "388") (name "/IN_P111") (class "Default")
      (node (ref "J1") (pin "156") (pinfunction "156_156") (pintype "bidirectional"))
    )
    (net (code "389") (name "/IN_P112") (class "Default")
      (node (ref "J1") (pin "14") (pinfunction "14_14") (pintype "bidirectional"))
    )
    (net (code "390") (name "/IN_P113") (class "Default")
      (node (ref "J1") (pin "157") (pinfunction "157_157") (pintype "bidirectional"))
    )
    (net (code "391") (name "/IN_P114") (class "Default")
      (node (ref "J1") (pin "13") (pinfunction "13_13") (pintype "bidirectional"))
    )
    (net (code "392") (name "/IN_P115") (class "Default")
      (node (ref "J1") (pin "12") (pinfunction "12_12") (pintype "bidirectional"))
    )
    (net (code "393") (name "/IN_P116") (class "Default")
      (node (ref "J1") (pin "159") (pinfunction "159_159") (pintype "bidirectional"))
    )
    (net (code "394") (name "/IN_P117") (class "Default")
      (node (ref "J1") (pin "11") (pinfunction "11_11") (pintype "bidirectional"))
    )
    (net (code "395") (name "/IN_P118") (class "Default")
      (node (ref "J1") (pin "160") (pinfunction "160_160") (pintype "bidirectional"))
    )
    (net (code "396") (name "/IN_P119") (class "Default")
      (node (ref "J1") (pin "10") (pinfunction "10_10") (pintype "bidirectional"))
    )
    (net (code "397") (name "/IN_P120") (class "Default")
      (node (ref "J1") (pin "9") (pinfunction "9_9") (pintype "bidirectional"))
    )
    (net (code "398") (name "/IN_P121") (class "Default")
      (node (ref "J1") (pin "162") (pinfunction "162_162") (pintype "bidirectional"))
    )
    (net (code "399") (name "/IN_P122") (class "Default")
      (node (ref "J1") (pin "8") (pinfunction "8_8") (pintype "bidirectional"))
    )
    (net (code "400") (name "/IN_P123") (class "Default")
      (node (ref "J1") (pin "163") (pinfunction "163_163") (pintype "bidirectional"))
    )
    (net (code "401") (name "/IN_P124") (class "Default")
      (node (ref "J1") (pin "7") (pinfunction "7_7") (pintype "bidirectional"))
    )
    (net (code "402") (name "/IN_P125") (class "Default")
      (node (ref "J1") (pin "6") (pinfunction "6_6") (pintype "bidirectional"))
    )
    (net (code "403") (name "/IN_P126") (class "Default")
      (node (ref "J1") (pin "165") (pinfunction "165_165") (pintype "bidirectional"))
    )
    (net (code "404") (name "/IN_P127") (class "Default")
      (node (ref "J1") (pin "5") (pinfunction "5_5") (pintype "bidirectional"))
    )
    (net (code "409") (name "/OUTP0") (class "Default")
      (node (ref "J2") (pin "1") (pinfunction "1_1") (pintype "bidirectional"))
    )
    (net (code "410") (name "/OUTP1") (class "Default")
      (node (ref "J2") (pin "2") (pinfunction "2_2") (pintype "bidirectional"))
    )
    (net (code "411") (name "/OUTP2") (class "Default")
      (node (ref "J2") (pin "3") (pinfunction "3_3") (pintype "bidirectional"))
    )
    (net (code "412") (name "/OUTP3") (class "Default")
      (node (ref "J2") (pin "4") (pinfunction "4_4") (pintype "bidirectional"))
    )
    (net (code "413") (name "/OUTP4") (class "Default")
      (node (ref "J2") (pin "5") (pinfunction "5_5") (pintype "bidirectional"))
    )
    (net (code "414") (name "/OUTP5") (class "Default")
      (node (ref "J2") (pin "6") (pinfunction "6_6") (pintype "bidirectional"))
    )
    (net (code "415") (name "/OUTP6") (class "Default")
      (node (ref "J2") (pin "7") (pinfunction "7_7") (pintype "bidirectional"))
    )
    (net (code "416") (name "/OUTP7") (class "Default")
      (node (ref "J2") (pin "8") (pinfunction "8_8") (pintype "bidirectional"))
    )
    (net (code "417") (name "/OUTP8") (class "Default")
      (node (ref "J2") (pin "9") (pinfunction "9_9") (pintype "bidirectional"))
    )
    (net (code "418") (name "/OUTP9") (class "Default")
      (node (ref "J2") (pin "10") (pinfunction "10_10") (pintype "bidirectional"))
    )
    (net (code "419") (name "/OUTP10") (class "Default")
      (node (ref "J2") (pin "11") (pinfunction "11_11") (pintype "bidirectional"))
    )
    (net (code "420") (name "/OUTP11") (class "Default")
      (node (ref "J2") (pin "12") (pinfunction "12_12") (pintype "bidirectional"))
    )
    (net (code "421") (name "/OUTP12") (class "Default")
      (node (ref "J2") (pin "13") (pinfunction "13_13") (pintype "bidirectional"))
    )
    (net (code "422") (name "/OUTP13") (class "Default")
      (node (ref "J2") (pin "14") (pinfunction "14_14") (pintype "bidirectional"))
    )
    (net (code "423") (name "/OUTP14") (class "Default")
      (node (ref "J2") (pin "15") (pinfunction "15_15") (pintype "bidirectional"))
    )
    (net (code "424") (name "/OUTP15") (class "Default")
      (node (ref "J2") (pin "16") (pinfunction "16_16") (pintype "bidirectional"))
    )
    (net (code "425") (name "/OUTP16") (class "Default")
      (node (ref "J2") (pin "17") (pinfunction "17_17") (pintype "bidirectional"))
    )
    (net (code "426") (name "/OUTP17") (class "Default")
      (node (ref "J2") (pin "18") (pinfunction "18_18") (pintype "bidirectional"))
    )
    (net (code "427") (name "/OUTP18") (class "Default")
      (node (ref "J2") (pin "19") (pinfunction "19_19") (pintype "bidirectional"))
    )
    (net (code "428") (name "/OUTP19") (class "Default")
      (node (ref "J2") (pin "20") (pinfunction "20_20") (pintype "bidirectional"))
    )
    (net (code "429") (name "/OUTP20") (class "Default")
      (node (ref "J2") (pin "21") (pinfunction "21_21") (pintype "bidirectional"))
    )
    (net (code "430") (name "/OUTP21") (class "Default")
      (node (ref "J2") (pin "22") (pinfunction "22_22") (pintype "bidirectional"))
    )
    (net (code "431") (name "/OUTP22") (class "Default")
      (node (ref "J2") (pin "23") (pinfunction "23_23") (pintype "bidirectional"))
    )
    (net (code "432") (name "/OUTP23") (class "Default")
      (node (ref "J2") (pin "24") (pinfunction "24_24") (pintype "bidirectional"))
    )
    (net (code "433") (name "/OUTP24") (class "Default")
      (node (ref "J2") (pin "25") (pinfunction "25_25") (pintype "bidirectional"))
    )
    (net (code "434") (name "/OUTP25") (class "Default")
      (node (ref "J2") (pin "26") (pinfunction "26_26") (pintype "bidirectional"))
    )
    (net (code "435") (name "/OUTP26") (class "Default")
      (node (ref "J2") (pin "27") (pinfunction "27_27") (pintype "bidirectional"))
    )
    (net (code "436") (name "/OUTP27") (class "Default")
      (node (ref "J2") (pin "28") (pinfunction "28_28") (pintype "bidirectional"))
    )
    (net (code "437") (name "/OUTP28") (class "Default")
      (node (ref "J2") (pin "29") (pinfunction "29_29") (pintype "bidirectional"))
    )
    (net (code "438") (name "/OUTP29") (class "Default")
      (node (ref "J2") (pin "30") (pinfunction "30_30") (pintype "bidirectional"))
    )
    (net (code "439") (name "/OUTP30") (class "Default")
      (node (ref "J2") (pin "31") (pinfunction "31_31") (pintype "bidirectional"))
    )
    (net (code "440") (name "/OUTP31") (class "Default")
      (node (ref "J2") (pin "32") (pinfunction "32_32") (pintype "bidirectional"))
    )
    (net (code "441") (name "/OUTP32") (class "Default")
      (node (ref "J2") (pin "48") (pinfunction "48_48") (pintype "bidirectional"))
    )
    (net (code "442") (name "/OUTP33") (class "Default")
      (node (ref "J2") (pin "49") (pinfunction "49_49") (pintype "bidirectional"))
    )
    (net (code "443") (name "/OUTP34") (class "Default")
      (node (ref "J2") (pin "50") (pinfunction "50_50") (pintype "bidirectional"))
    )
    (net (code "444") (name "/OUTP35") (class "Default")
      (node (ref "J2") (pin "51") (pinfunction "51_51") (pintype "bidirectional"))
    )
    (net (code "445") (name "/OUTP36") (class "Default")
      (node (ref "J2") (pin "52") (pinfunction "52_52") (pintype "bidirectional"))
    )
    (net (code "446") (name "/OUTP37") (class "Default")
      (node (ref "J2") (pin "53") (pinfunction "53_53") (pintype "bidirectional"))
    )
    (net (code "447") (name "/OUTP38") (class "Default")
      (node (ref "J2") (pin "54") (pinfunction "54_54") (pintype "bidirectional"))
    )
    (net (code "448") (name "/OUTP39") (class "Default")
      (node (ref "J2") (pin "55") (pinfunction "55_55") (pintype "bidirectional"))
    )
    (net (code "449") (name "/OUTP40") (class "Default")
      (node (ref "J2") (pin "56") (pinfunction "56_56") (pintype "bidirectional"))
    )
    (net (code "450") (name "/OUTP41") (class "Default")
      (node (ref "J2") (pin "57") (pinfunction "57_57") (pintype "bidirectional"))
    )
    (net (code "451") (name "/OUTP42") (class "Default")
      (node (ref "J2") (pin "58") (pinfunction "58_58") (pintype "bidirectional"))
    )
    (net (code "452") (name "/OUTP43") (class "Default")
      (node (ref "J2") (pin "59") (pinfunction "59_59") (pintype "bidirectional"))
    )
    (net (code "453") (name "/OUTP44") (class "Default")
      (node (ref "J2") (pin "60") (pinfunction "60_60") (pintype "bidirectional"))
    )
    (net (code "454") (name "/OUTP45") (class "Default")
      (node (ref "J2") (pin "61") (pinfunction "61_61") (pintype "bidirectional"))
    )
    (net (code "455") (name "/OUTP46") (class "Default")
      (node (ref "J2") (pin "62") (pinfunction "62_62") (pintype "bidirectional"))
    )
    (net (code "456") (name "/OUTP47") (class "Default")
      (node (ref "J2") (pin "63") (pinfunction "63_63") (pintype "bidirectional"))
    )
    (net (code "457") (name "/OUTP48") (class "Default")
      (node (ref "J2") (pin "64") (pinfunction "64_64") (pintype "bidirectional"))
    )
    (net (code "458") (name "/OUTP49") (class "Default")
      (node (ref "J2") (pin "65") (pinfunction "65_65") (pintype "bidirectional"))
    )
    (net (code "459") (name "/OUTP50") (class "Default")
      (node (ref "J2") (pin "66") (pinfunction "66_66") (pintype "bidirectional"))
    )
    (net (code "460") (name "/OUTP51") (class "Default")
      (node (ref "J2") (pin "67") (pinfunction "67_67") (pintype "bidirectional"))
    )
    (net (code "461") (name "/OUTP52") (class "Default")
      (node (ref "J2") (pin "68") (pinfunction "68_68") (pintype "bidirectional"))
    )
    (net (code "462") (name "/OUTP53") (class "Default")
      (node (ref "J2") (pin "69") (pinfunction "69_69") (pintype "bidirectional"))
    )
    (net (code "463") (name "/OUTP54") (class "Default")
      (node (ref "J2") (pin "70") (pinfunction "70_70") (pintype "bidirectional"))
    )
    (net (code "464") (name "/OUTP55") (class "Default")
      (node (ref "J2") (pin "71") (pinfunction "71_71") (pintype "bidirectional"))
    )
    (net (code "465") (name "/OUTP56") (class "Default")
      (node (ref "J2") (pin "72") (pinfunction "72_72") (pintype "bidirectional"))
    )
    (net (code "466") (name "/OUTP57") (class "Default")
      (node (ref "J2") (pin "73") (pinfunction "73_73") (pintype "bidirectional"))
    )
    (net (code "467") (name "/OUTP58") (class "Default")
      (node (ref "J2") (pin "74") (pinfunction "74_74") (pintype "bidirectional"))
    )
    (net (code "468") (name "/OUTP59") (class "Default")
      (node (ref "J2") (pin "75") (pinfunction "75_75") (pintype "bidirectional"))
    )
    (net (code "469") (name "/OUTP60") (class "Default")
      (node (ref "J2") (pin "76") (pinfunction "76_76") (pintype "bidirectional"))
    )
    (net (code "470") (name "/OUTP61") (class "Default")
      (node (ref "J2") (pin "77") (pinfunction "77_77") (pintype "bidirectional"))
    )
    (net (code "471") (name "/OUTP62") (class "Default")
      (node (ref "J2") (pin "78") (pinfunction "78_78") (pintype "bidirectional"))
    )
    (net (code "472") (name "/OUTP63") (class "Default")
      (node (ref "J2") (pin "79") (pinfunction "79_79") (pintype "bidirectional"))
    )
    (net (code "473") (name "/OUTP64") (class "Default")
      (node (ref "J2") (pin "100") (pinfunction "100_100") (pintype "bidirectional"))
    )
    (net (code "474") (name "/OUTP65") (class "Default")
      (node (ref "J2") (pin "101") (pinfunction "101_101") (pintype "bidirectional"))
    )
    (net (code "475") (name "/OUTP66") (class "Default")
      (node (ref "J2") (pin "102") (pinfunction "102_102") (pintype "bidirectional"))
    )
    (net (code "476") (name "/OUTP67") (class "Default")
      (node (ref "J2") (pin "103") (pinfunction "103_103") (pintype "bidirectional"))
    )
    (net (code "477") (name "/OUTP68") (class "Default")
      (node (ref "J2") (pin "104") (pinfunction "104_104") (pintype "bidirectional"))
    )
    (net (code "478") (name "/OUTP69") (class "Default")
      (node (ref "J2") (pin "105") (pinfunction "105_105") (pintype "bidirectional"))
    )
    (net (code "479") (name "/OUTP70") (class "Default")
      (node (ref "J2") (pin "106") (pinfunction "106_106") (pintype "bidirectional"))
    )
    (net (code "480") (name "/OUTP71") (class "Default")
      (node (ref "J2") (pin "107") (pinfunction "107_107") (pintype "bidirectional"))
    )
    (net (code "481") (name "/OUTP72") (class "Default")
      (node (ref "J2") (pin "108") (pinfunction "108_108") (pintype "bidirectional"))
    )
    (net (code "482") (name "/OUTP73") (class "Default")
      (node (ref "J2") (pin "109") (pinfunction "109_109") (pintype "bidirectional"))
    )
    (net (code "483") (name "/OUTP74") (class "Default")
      (node (ref "J2") (pin "110") (pinfunction "110_110") (pintype "bidirectional"))
    )
    (net (code "484") (name "/OUTP75") (class "Default")
      (node (ref "J2") (pin "111") (pinfunction "111_111") (pintype "bidirectional"))
    )
    (net (code "485") (name "/OUTP76") (class "Default")
      (node (ref "J2") (pin "112") (pinfunction "112_112") (pintype "bidirectional"))
    )
    (net (code "486") (name "/OUTP77") (class "Default")
      (node (ref "J2") (pin "113") (pinfunction "113_113") (pintype "bidirectional"))
    )
    (net (code "487") (name "/OUTP78") (class "Default")
      (node (ref "J2") (pin "114") (pinfunction "114_114") (pintype "bidirectional"))
    )
    (net (code "488") (name "/OUTP79") (class "Default")
      (node (ref "J2") (pin "115") (pinfunction "115_115") (pintype "bidirectional"))
    )
    (net (code "489") (name "/OUTP80") (class "Default")
      (node (ref "J2") (pin "116") (pinfunction "116_116") (pintype "bidirectional"))
    )
    (net (code "490") (name "/OUTP81") (class "Default")
      (node (ref "J2") (pin "117") (pinfunction "117_117") (pintype "bidirectional"))
    )
    (net (code "491") (name "/OUTP82") (class "Default")
      (node (ref "J2") (pin "118") (pinfunction "118_118") (pintype "bidirectional"))
    )
    (net (code "492") (name "/OUTP83") (class "Default")
      (node (ref "J2") (pin "119") (pinfunction "119_119") (pintype "bidirectional"))
    )
    (net (code "493") (name "/OUTP84") (class "Default")
      (node (ref "J2") (pin "120") (pinfunction "120_120") (pintype "bidirectional"))
    )
    (net (code "494") (name "/OUTP85") (class "Default")
      (node (ref "J2") (pin "121") (pinfunction "121_121") (pintype "bidirectional"))
    )
    (net (code "495") (name "/OUTP86") (class "Default")
      (node (ref "J2") (pin "122") (pinfunction "122_122") (pintype "bidirectional"))
    )
    (net (code "496") (name "/OUTP87") (class "Default")
      (node (ref "J2") (pin "123") (pinfunction "123_123") (pintype "bidirectional"))
    )
    (net (code "497") (name "/OUTP88") (class "Default")
      (node (ref "J2") (pin "124") (pinfunction "124_124") (pintype "bidirectional"))
    )
    (net (code "498") (name "/OUTP89") (class "Default")
      (node (ref "J2") (pin "125") (pinfunction "125_125") (pintype "bidirectional"))
    )
    (net (code "499") (name "/OUTP90") (class "Default")
      (node (ref "J2") (pin "126") (pinfunction "126_126") (pintype "bidirectional"))
    )
    (net (code "500") (name "/OUTP91") (class "Default")
      (node (ref "J2") (pin "127") (pinfunction "127_127") (pintype "bidirectional"))
    )
    (net (code "501") (name "/OUTP92") (class "Default")
      (node (ref "J2") (pin "128") (pinfunction "128_128") (pintype "bidirectional"))
    )
    (net (code "502") (name "/OUTP93") (class "Default")
      (node (ref "J2") (pin "129") (pinfunction "129_129") (pintype "bidirectional"))
    )
    (net (code "503") (name "/OUTP94") (class "Default")
      (node (ref "J2") (pin "130") (pinfunction "130_130") (pintype "bidirectional"))
    )
    (net (code "504") (name "/OUTP95") (class "Default")
      (node (ref "J2") (pin "131") (pinfunction "131_131") (pintype "bidirectional"))
    )
    (net (code "505") (name "/OUTP96") (class "Default")
      (node (ref "J2") (pin "149") (pinfunction "149_149") (pintype "bidirectional"))
    )
    (net (code "506") (name "/OUTP97") (class "Default")
      (node (ref "J2") (pin "150") (pinfunction "150_150") (pintype "bidirectional"))
    )
    (net (code "507") (name "/OUTP98") (class "Default")
      (node (ref "J2") (pin "151") (pinfunction "151_151") (pintype "bidirectional"))
    )
    (net (code "508") (name "/OUTP99") (class "Default")
      (node (ref "J2") (pin "152") (pinfunction "152_152") (pintype "bidirectional"))
    )
    (net (code "509") (name "/OUTP100") (class "Default")
      (node (ref "J2") (pin "153") (pinfunction "153_153") (pintype "bidirectional"))
    )
    (net (code "510") (name "/OUTP101") (class "Default")
      (node (ref "J2") (pin "154") (pinfunction "154_154") (pintype "bidirectional"))
    )
    (net (code "511") (name "/OUTP102") (class "Default")
      (node (ref "J2") (pin "155") (pinfunction "155_155") (pintype "bidirectional"))
    )
    (net (code "512") (name "/OUTP103") (class "Default")
      (node (ref "J2") (pin "156") (pinfunction "156_156") (pintype "bidirectional"))
    )
    (net (code "513") (name "/OUTP104") (class "Default")
      (node (ref "J2") (pin "157") (pinfunction "157_157") (pintype "bidirectional"))
    )
    (net (code "514") (name "/OUTP105") (class "Default")
      (node (ref "J2") (pin "158") (pinfunction "158_158") (pintype "bidirectional"))
    )
    (net (code "515") (name "/OUTP106") (class "Default")
      (node (ref "J2") (pin "159") (pinfunction "159_159") (pintype "bidirectional"))
    )
    (net (code "516") (name "/OUTP107") (class "Default")
      (node (ref "J2") (pin "160") (pinfunction "160_160") (pintype "bidirectional"))
    )
    (net (code "517") (name "/OUTP108") (class "Default")
      (node (ref "J2") (pin "161") (pinfunction "161_161") (pintype "bidirectional"))
    )
    (net (code "518") (name "/OUTP109") (class "Default")
      (node (ref "J2") (pin "162") (pinfunction "162_162") (pintype "bidirectional"))
    )
    (net (code "519") (name "/OUTP110") (class "Default")
      (node (ref "J2") (pin "163") (pinfunction "163_163") (pintype "bidirectional"))
    )
    (net (code "520") (name "/OUTP111") (class "Default")
      (node (ref "J2") (pin "164") (pinfunction "164_164") (pintype "bidirectional"))
    )
    (net (code "521") (name "/OUTP112") (class "Default")
      (node (ref "J2") (pin "165") (pinfunction "165_165") (pintype "bidirectional"))
    )
    (net (code "522") (name "/OUTP113") (class "Default")
      (node (ref "J2") (pin "166") (pinfunction "166_166") (pintype "bidirectional"))
    )
    (net (code "523") (name "/OUTP114") (class "Default")
      (node (ref "J2") (pin "167") (pinfunction "167_167") (pintype "bidirectional"))
    )
    (net (code "524") (name "/OUTP115") (class "Default")
      (node (ref "J2") (pin "168") (pinfunction "168_168") (pintype "bidirectional"))
    )
    (net (code "525") (name "/OUTP116") (class "Default")
      (node (ref "J2") (pin "169") (pinfunction "169_169") (pintype "bidirectional"))
    )
    (net (code "526") (name "/OUTP117") (class "Default")
      (node (ref "J2") (pin "170") (pinfunction "170_170") (pintype "bidirectional"))
    )
    (net (code "527") (name "/OUTP118") (class "Default")
      (node (ref "J2") (pin "171") (pinfunction "171_171") (pintype "bidirectional"))
    )
    (net (code "528") (name "/OUTP119") (class "Default")
      (node (ref "J2") (pin "172") (pinfunction "172_172") (pintype "bidirectional"))
    )
    (net (code "529") (name "/OUTP120") (class "Default")
      (node (ref "J2") (pin "173") (pinfunction "173_173") (pintype "bidirectional"))
    )
    (net (code "530") (name "/OUTP121") (class "Default")
      (node (ref "J2") (pin "174") (pinfunction "174_174") (pintype "bidirectional"))
    )
    (net (code "531") (name "/OUTP122") (class "Default")
      (node (ref "J2") (pin "175") (pinfunction "175_175") (pintype "bidirectional"))
    )
    (net (code "532") (name "/OUTP123") (class "Default")
      (node (ref "J2") (pin "176") (pinfunction "176_176") (pintype "bidirectional"))
    )
    (net (code "533") (name "/OUTP124") (class "Default")
      (node (ref "J2") (pin "177") (pinfunction "177_177") (pintype "bidirectional"))
    )
    (net (code "534") (name "/OUTP125") (class "Default")
      (node (ref "J2") (pin "178") (pinfunction "178_178") (pintype "bidirectional"))
    )
    (net (code "535") (name "/OUTP126") (class "Default")
      (node (ref "J2") (pin "179") (pinfunction "179_179") (pintype "bidirectional"))
    )
    (net (code "536") (name "/OUTP127") (class "Default")
      (node (ref "J2") (pin "180") (pinfunction "180_180") (pintype "bidirectional"))
    )
    (net (code "538") (name "/RCLK") (class "Default")
      (node (ref "R26") (pin "2") (pinfunction "2_2") (pintype "passive"))
    )
    (net (code "539") (name "/SCL") (class "Default")
      (node (ref "IC31") (pin "2") (pinfunction "SCL_2") (pintype "input"))
      (node (ref "IC32") (pin "2") (pinfunction "SCL_2") (pintype "input"))
      (node (ref "J2") (pin "45") (pinfunction "45_45") (pintype "bidirectional"))
    )
    (net (code "540") (name "/SDA") (class "Default")
      (node (ref "IC31") (pin "1") (pinfunction "SDA_1") (pintype "bidirectional"))
      (node (ref "IC32") (pin "1") (pinfunction "SDA_1") (pintype "bidirectional"))
      (node (ref "J2") (pin "44") (pinfunction "44_44") (pintype "bidirectional"))
    )
    (net (code "545") (name "3P3VAUX") (class "Default")
      (node (ref "J2") (pin "41") (pinfunction "41_41") (pintype "bidirectional"))
    )
    (net (code "546") (name "GND") (class "Default")
      (node (ref "C95") (pin "1") (pinfunction "1_1") (pintype "passive"))
      (node (ref "C96") (pin "1") (pinfunction "1_1") (pintype "passive"))
      (node (ref "IC31") (pin "13") (pinfunction "VSS_13") (pintype "power_in"))
      (node (ref "IC31") (pin "5") (pinfunction "A2_5") (pintype "bidirectional"))
      (node (ref "IC31") (pin "6") (pinfunction "A1_6") (pintype "input"))
      (node (ref "IC32") (pin "13") (pinfunction "VSS_13") (pintype "power_in"))
      (node (ref "IC32") (pin "5") (pinfunction "A2_5") (pintype "bidirectional"))
      (node (ref "IC32") (pin "6") (pinfunction "A1_6") (pintype "input"))
      (node (ref "IC32") (pin "7") (pinfunction "A0_7") (pintype "input"))
      (node (ref "J1") (pin "101") (pinfunction "101_101") (pintype "bidirectional"))
      (node (ref "J1") (pin "104") (pinfunction "104_104") (pintype "bidirectional"))
      (node (ref "J1") (pin "107") (pinfunction "107_107") (pintype "bidirectional"))
      (node (ref "J1") (pin "110") (pinfunction "110_110") (pintype "bidirectional"))
      (node (ref "J1") (pin "113") (pinfunction "113_113") (pintype "bidirectional"))
      (node (ref "J1") (pin "116") (pinfunction "116_116") (pintype "bidirectional"))
      (node (ref "J1") (pin "119") (pinfunction "119_119") (pintype "bidirectional"))
      (node (ref "J1") (pin "122") (pinfunction "122_122") (pintype "bidirectional"))
      (node (ref "J1") (pin "125") (pinfunction "125_125") (pintype "bidirectional"))
      (node (ref "J1") (pin "128") (pinfunction "128_128") (pintype "bidirectional"))
      (node (ref "J1") (pin "131") (pinfunction "131_131") (pintype "bidirectional"))
      (node (ref "J1") (pin "134") (pinfunction "134_134") (pintype "bidirectional"))
      (node (ref "J1") (pin "137") (pinfunction "137_137") (pintype "bidirectional"))
      (node (ref "J1") (pin "140") (pinfunction "140_140") (pintype "bidirectional"))
      (node (ref "J1") (pin "143") (pinfunction "143_143") (pintype "bidirectional"))
      (node (ref "J1") (pin "146") (pinfunction "146_146") (pintype "bidirectional"))
      (node (ref "J1") (pin "149") (pinfunction "149_149") (pintype "bidirectional"))
      (node (ref "J1") (pin "152") (pinfunction "152_152") (pintype "bidirectional"))
      (node (ref "J1") (pin "155") (pinfunction "155_155") (pintype "bidirectional"))
      (node (ref "J1") (pin "158") (pinfunction "158_158") (pintype "bidirectional"))
      (node (ref "J1") (pin "161") (pinfunction "161_161") (pintype "bidirectional"))
      (node (ref "J1") (pin "164") (pinfunction "164_164") (pintype "bidirectional"))
      (node (ref "J1") (pin "166") (pinfunction "166_166") (pintype "bidirectional"))
      (node (ref "J1") (pin "167") (pinfunction "167_167") (pintype "bidirectional"))
      (node (ref "J1") (pin "168") (pinfunction "168_168") (pintype "bidirectional"))
      (node (ref "J1") (pin "169") (pinfunction "169_169") (pintype "bidirectional"))
      (node (ref "J1") (pin "170") (pinfunction "170_170") (pintype "bidirectional"))
      (node (ref "J1") (pin "86") (pinfunction "86_86") (pintype "bidirectional"))
      (node (ref "J1") (pin "87") (pinfunction "87_87") (pintype "bidirectional"))
      (node (ref "J1") (pin "88") (pinfunction "88_88") (pintype "bidirectional"))
      (node (ref "J1") (pin "89") (pinfunction "89_89") (pintype "bidirectional"))
      (node (ref "J1") (pin "92") (pinfunction "92_92") (pintype "bidirectional"))
      (node (ref "J1") (pin "95") (pinfunction "95_95") (pintype "bidirectional"))
      (node (ref "J1") (pin "98") (pinfunction "98_98") (pintype "bidirectional"))
      (node (ref "J2") (pin "132") (pinfunction "132_132") (pintype "bidirectional"))
      (node (ref "J2") (pin "134") (pinfunction "134_134") (pintype "bidirectional"))
      (node (ref "J2") (pin "135") (pinfunction "135_135") (pintype "bidirectional"))
      (node (ref "J2") (pin "136") (pinfunction "136_136") (pintype "bidirectional"))
      (node (ref "J2") (pin "137") (pinfunction "137_137") (pintype "bidirectional"))
      (node (ref "J2") (pin "139") (pinfunction "139_139") (pintype "bidirectional"))
      (node (ref "J2") (pin "140") (pinfunction "140_140") (pintype "bidirectional"))
      (node (ref "J2") (pin "141") (pinfunction "141_141") (pintype "bidirectional"))
      (node (ref "J2") (pin "143") (pinfunction "143_143") (pintype "bidirectional"))
      (node (ref "J2") (pin "144") (pinfunction "144_144") (pintype "bidirectional"))
      (node (ref "J2") (pin "145") (pinfunction "145_145") (pintype "bidirectional"))
      (node (ref "J2") (pin "147") (pinfunction "147_147") (pintype "bidirectional"))
      (node (ref "J2") (pin "148") (pinfunction "148_148") (pintype "bidirectional"))
      (node (ref "J2") (pin "181") (pinfunction "181_181") (pintype "bidirectional"))
      (node (ref "J2") (pin "182") (pinfunction "182_182") (pintype "bidirectional"))
      (node (ref "J2") (pin "183") (pinfunction "183_183") (pintype "bidirectional"))
      (node (ref "J2") (pin "184") (pinfunction "184_184") (pintype "bidirectional"))
      (node (ref "J2") (pin "185") (pinfunction "185_185") (pintype "bidirectional"))
      (node (ref "J2") (pin "186") (pinfunction "186_186") (pintype "bidirectional"))
      (node (ref "J2") (pin "187") (pinfunction "187_187") (pintype "bidirectional"))
      (node (ref "J2") (pin "188") (pinfunction "188_188") (pintype "bidirectional"))
      (node (ref "J2") (pin "189") (pinfunction "189_189") (pintype "bidirectional"))
      (node (ref "J2") (pin "190") (pinfunction "190_190") (pintype "bidirectional"))
      (node (ref "J2") (pin "191") (pinfunction "191_191") (pintype "bidirectional"))
      (node (ref "J2") (pin "192") (pinfunction "192_192") (pintype "bidirectional"))
      (node (ref "J2") (pin "193") (pinfunction "193_193") (pintype "bidirectional"))
      (node (ref "J2") (pin "194") (pinfunction "194_194") (pintype "bidirectional"))
      (node (ref "J2") (pin "195") (pinfunction "195_195") (pintype "bidirectional"))
      (node (ref "J2") (pin "196") (pinfunction "196_196") (pintype "bidirectional"))
      (node (ref "J2") (pin "197") (pinfunction "197_197") (pintype "bidirectional"))
      (node (ref "J2") (pin "198") (pinfunction "198_198") (pintype "bidirectional"))
      (node (ref "J2") (pin "199") (pinfunction "199_199") (pintype "bidirectional"))
      (node (ref "J2") (pin "200") (pinfunction "200_200") (pintype "bidirectional"))
      (node (ref "J2") (pin "201") (pinfunction "201_201") (pintype "bidirectional"))
      (node (ref "J2") (pin "202") (pinfunction "202_202") (pintype "bidirectional"))
      (node (ref "J2") (pin "203") (pinfunction "203_203") (pintype "bidirectional"))
      (node (ref "J2") (pin "204") (pinfunction "204_204") (pintype "bidirectional"))
      (node (ref "J2") (pin "33") (pinfunction "33_33") (pintype "bidirectional"))
      (node (ref "J2") (pin "34") (pinfunction "34_34") (pintype "bidirectional"))
      (node (ref "J2") (pin "36") (pinfunction "36_36") (pintype "bidirectional"))
      (node (ref "J2") (pin "37") (pinfunction "37_37") (pintype "bidirectional"))
      (node (ref "J2") (pin "38") (pinfunction "38_38") (pintype "bidirectional"))
      (node (ref "J2") (pin "39") (pinfunction "39_39") (pintype "bidirectional"))
      (node (ref "J2") (pin "40") (pinfunction "40_40") (pintype "bidirectional"))
      (node (ref "J2") (pin "42") (pinfunction "42_42") (pintype "bidirectional"))
      (node (ref "J2") (pin "43") (pinfunction "43_43") (pintype "bidirectional"))
      (node (ref "J2") (pin "46") (pinfunction "46_46") (pintype "bidirectional"))
      (node (ref "J2") (pin "47") (pinfunction "47_47") (pintype "bidirectional"))
      (node (ref "J2") (pin "80") (pinfunction "80_80") (pintype "bidirectional"))
      (node (ref "J2") (pin "81") (pinfunction "81_81") (pintype "bidirectional"))
      (node (ref "J2") (pin "83") (pinfunction "83_83") (pintype "bidirectional"))
      (node (ref "J2") (pin "84") (pinfunction "84_84") (pintype "bidirectional"))
      (node (ref "J2") (pin "96") (pinfunction "96_96") (pintype "bidirectional"))
      (node (ref "J2") (pin "97") (pinfunction "97_97") (pintype "bidirectional"))
      (node (ref "J2") (pin "99") (pinfunction "99_99") (pintype "bidirectional"))
      (node (ref "R43") (pin "1") (pinfunction "1_1") (pintype "passive"))
      (node (ref "R44") (pin "1") (pinfunction "1_1") (pintype "passive"))
      (node (ref "R45") (pin "1") (pinfunction "1_1") (pintype "passive"))
      (node (ref "T1") (pin "2") (pinfunction "S_2") (pintype "passive"))
    )
    (net (code "547") (name "Net-(IC31-MISO)") (class "Default")
      (node (ref "IC31") (pin "14") (pinfunction "MISO_14") (pintype "input"))
      (node (ref "R28") (pin "2") (pinfunction "2_2") (pintype "passive"))
    )
    (net (code "548") (name "Net-(IC31-MOSI)") (class "Default")
      (node (ref "IC31") (pin "10") (pinfunction "MOSI_10") (pintype "output"))
      (node (ref "R29") (pin "2") (pinfunction "2_2") (pintype "passive"))
    )
    (net (code "549") (name "Net-(IC31-SPICLK)") (class "Default")
      (node (ref "IC31") (pin "11") (pinfunction "SPICLK_11") (pintype "output"))
      (node (ref "R30") (pin "1") (pinfunction "1_1") (pintype "passive"))
    )
    (net (code "550") (name "Net-(IC31-~{SS0}{slash}GPIO0)") (class "Default")
      (node (ref "IC31") (pin "9") (pinfunction "~{SS0}/GPIO0_9") (pintype "bidirectional"))
      (node (ref "R38") (pin "1") (pinfunction "1_1") (pintype "passive"))
    )
    (net (code "551") (name "Net-(IC31-~{SS1}{slash}GPIO1)") (class "Default")
      (node (ref "IC31") (pin "16") (pinfunction "~{SS1}/GPIO1_16") (pintype "bidirectional"))
      (node (ref "R27") (pin "2") (pinfunction "2_2") (pintype "passive"))
    )
    (net (code "552") (name "Net-(IC31-~{SS2}{slash}GPIO2)") (class "Default")
      (node (ref "IC31") (pin "8") (pinfunction "~{SS2}/GPIO2_8") (pintype "bidirectional"))
      (node (ref "R31") (pin "1") (pinfunction "1_1") (pintype "passive"))
    )
    (net (code "553") (name "Net-(IC32-MISO)") (class "Default")
      (node (ref "IC32") (pin "14") (pinfunction "MISO_14") (pintype "input"))
      (node (ref "R35") (pin "2") (pinfunction "2_2") (pintype "passive"))
    )
    (net (code "554") (name "Net-(IC32-MOSI)") (class "Default")
      (node (ref "IC32") (pin "10") (pinfunction "MOSI_10") (pintype "output"))
      (node (ref "R36") (pin "2") (pinfunction "2_2") (pintype "passive"))
    )
    (net (code "555") (name "Net-(IC32-SPICLK)") (class "Default")
      (node (ref "IC32") (pin "11") (pinfunction "SPICLK_11") (pintype "output"))
      (node (ref "R37") (pin "1") (pinfunction "1_1") (pintype "passive"))
    )
    (net (code "556") (name "Net-(IC32-~{SS0}{slash}GPIO0)") (class "Default")
      (node (ref "IC32") (pin "9") (pinfunction "~{SS0}/GPIO0_9") (pintype "bidirectional"))
      (node (ref "R32") (pin "2") (pinfunction "2_2") (pintype "passive"))
    )
    (net (code "557") (name "Net-(IC32-~{SS1}{slash}GPIO1)") (class "Default")
      (node (ref "IC32") (pin "16") (pinfunction "~{SS1}/GPIO1_16") (pintype "bidirectional"))
      (node (ref "R33") (pin "2") (pinfunction "2_2") (pintype "passive"))
    )
    (net (code "558") (name "Net-(IC32-~{SS2}{slash}GPIO2)") (class "Default")
      (node (ref "IC32") (pin "8") (pinfunction "~{SS2}/GPIO2_8") (pintype "bidirectional"))
      (node (ref "R34") (pin "1") (pinfunction "1_1") (pintype "passive"))
    )
    (net (code "559") (name "Net-(J2-Pad138)") (class "Default")
      (node (ref "J2") (pin "138") (pinfunction "138_138") (pintype "bidirectional"))
      (node (ref "TP4") (pin "1") (pinfunction "1_1") (pintype "bidirectional"))
    )
    (net (code "560") (name "Net-(J2-Pad142)") (class "Default")
      (node (ref "J2") (pin "142") (pinfunction "142_142") (pintype "bidirectional"))
      (node (ref "TP5") (pin "1") (pinfunction "1_1") (pintype "bidirectional"))
    )
    (net (code "561") (name "Net-(LD1-A)") (class "Default")
      (node (ref "LD1") (pin "2") (pinfunction "A_2") (pintype "passive"))
      (node (ref "R41") (pin "1") (pinfunction "1_1") (pintype "passive"))
    )
    (net (code "562") (name "Net-(LD1-C)") (class "Default")
      (node (ref "LD1") (pin "1") (pinfunction "C_1") (pintype "passive"))
      (node (ref "T1") (pin "3") (pinfunction "D_3") (pintype "passive"))
    )
    (net (code "563") (name "Net-(LD2-C)") (class "Default")
      (node (ref "LD2") (pin "1") (pinfunction "C_1") (pintype "passive"))
      (node (ref "R43") (pin "2") (pinfunction "2_2") (pintype "passive"))
    )
    (net (code "564") (name "Net-(LD3-C)") (class "Default")
      (node (ref "LD3") (pin "1") (pinfunction "C_1") (pintype "passive"))
      (node (ref "R44") (pin "2") (pinfunction "2_2") (pintype "passive"))
    )
    (net (code "565") (name "P1V8") (class "Default")
      (node (ref "J2") (pin "91") (pinfunction "91_91") (pintype "bidirectional"))
      (node (ref "J2") (pin "92") (pinfunction "92_92") (pintype "bidirectional"))
      (node (ref "J2") (pin "93") (pinfunction "93_93") (pintype "bidirectional"))
      (node (ref "J2") (pin "94") (pinfunction "94_94") (pintype "bidirectional"))
      (node (ref "J2") (pin "95") (pinfunction "95_95") (pintype "bidirectional"))
      (node (ref "R45") (pin "2") (pinfunction "2_2") (pintype "passive"))
      (node (ref "T1") (pin "1") (pinfunction "G_1") (pintype "passive"))
    )
    (net (code "566") (name "P3V3") (class "Default")
      (node (ref "C95") (pin "2") (pinfunction "2_2") (pintype "passive"))
      (node (ref "C96") (pin "2") (pinfunction "2_2") (pintype "passive"))
      (node (ref "IC31") (pin "12") (pinfunction "VDD_12") (pintype "power_in"))
      (node (ref "IC31") (pin "15") (pinfunction "VREFP_15") (pintype "power_in"))
      (node (ref "IC31") (pin "4") (pinfunction "~{RESET}_4") (pintype "input"))
      (node (ref "IC31") (pin "7") (pinfunction "A0_7") (pintype "input"))
      (node (ref "IC32") (pin "12") (pinfunction "VDD_12") (pintype "power_in"))
      (node (ref "IC32") (pin "15") (pinfunction "VREFP_15") (pintype "power_in"))
      (node (ref "IC32") (pin "4") (pinfunction "~{RESET}_4") (pintype "input"))
      (node (ref "J2") (pin "85") (pinfunction "85_85") (pintype "bidirectional"))
      (node (ref "J2") (pin "86") (pinfunction "86_86") (pintype "bidirectional"))
      (node (ref "J2") (pin "87") (pinfunction "87_87") (pintype "bidirectional"))
      (node (ref "J2") (pin "88") (pinfunction "88_88") (pintype "bidirectional"))
      (node (ref "J2") (pin "89") (pinfunction "89_89") (pintype "bidirectional"))
      (node (ref "J2") (pin "90") (pinfunction "90_90") (pintype "bidirectional"))
      (node (ref "R41") (pin "2") (pinfunction "2_2") (pintype "passive"))
      (node (ref "R56") (pin "2") (pinfunction "2_2") (pintype "passive"))
    )
    (net (code "567") (name "P12V0") (class "Default")
      (node (ref "J1") (pin "82") (pinfunction "82_82") (pintype "bidirectional"))
      (node (ref "J1") (pin "83") (pinfunction "83_83") (pintype "bidirectional"))
      (node (ref "J1") (pin "84") (pinfunction "84_84") (pintype "bidirectional"))
      (node (ref "J1") (pin "85") (pinfunction "85_85") (pintype "bidirectional"))
      (node (ref "LD2") (pin "2") (pinfunction "A_2") (pintype "passive"))
    )
    (net (code "568") (name "TIA_VCC") (class "Default")
      (node (ref "LD3") (pin "2") (pinfunction "A_2") (pintype "passive"))
    )
    (net (code "569") (name "unconnected-(B5-Pad1)") (class "Default")
      (node (ref "B5") (pin "1") (pinfunction "1_1") (pintype "bidirectional"))
    )
    (net (code "570") (name "unconnected-(B6-Pad1)") (class "Default")
      (node (ref "B6") (pin "1") (pinfunction "1_1") (pintype "bidirectional"))
    )
    (net (code "571") (name "unconnected-(B7-Pad1)") (class "Default")
      (node (ref "B7") (pin "1") (pinfunction "1_1") (pintype "bidirectional"))
    )
    (net (code "572") (name "unconnected-(B8-Pad1)") (class "Default")
      (node (ref "B8") (pin "1") (pinfunction "1_1") (pintype "bidirectional"))
    )
    (net (code "573") (name "unconnected-(IC31-~{INT}-Pad3)") (class "Default")
      (node (ref "IC31") (pin "3") (pinfunction "~{INT}_3") (pintype "output+no_connect"))
    )
    (net (code "574") (name "unconnected-(IC32-~{INT}-Pad3)") (class "Default")
      (node (ref "IC32") (pin "3") (pinfunction "~{INT}_3") (pintype "output"))
    )
    (net (code "575") (name "unconnected-(J1-Pad1)") (class "Default")
      (node (ref "J1") (pin "1") (pinfunction "1_1") (pintype "bidirectional"))
    )
    (net (code "576") (name "unconnected-(J1-Pad2)") (class "Default")
      (node (ref "J1") (pin "2") (pinfunction "2_2") (pintype "bidirectional"))
    )
    (net (code "577") (name "unconnected-(J1-Pad3)") (class "Default")
      (node (ref "J1") (pin "3") (pinfunction "3_3") (pintype "bidirectional"))
    )
    (net (code "578") (name "unconnected-(J1-Pad4)") (class "Default")
      (node (ref "J1") (pin "4") (pinfunction "4_4") (pintype "bidirectional"))
    )
  )
)
